# Ethernet.net
KiCad netlist of a schematic drawn in Altium Designer
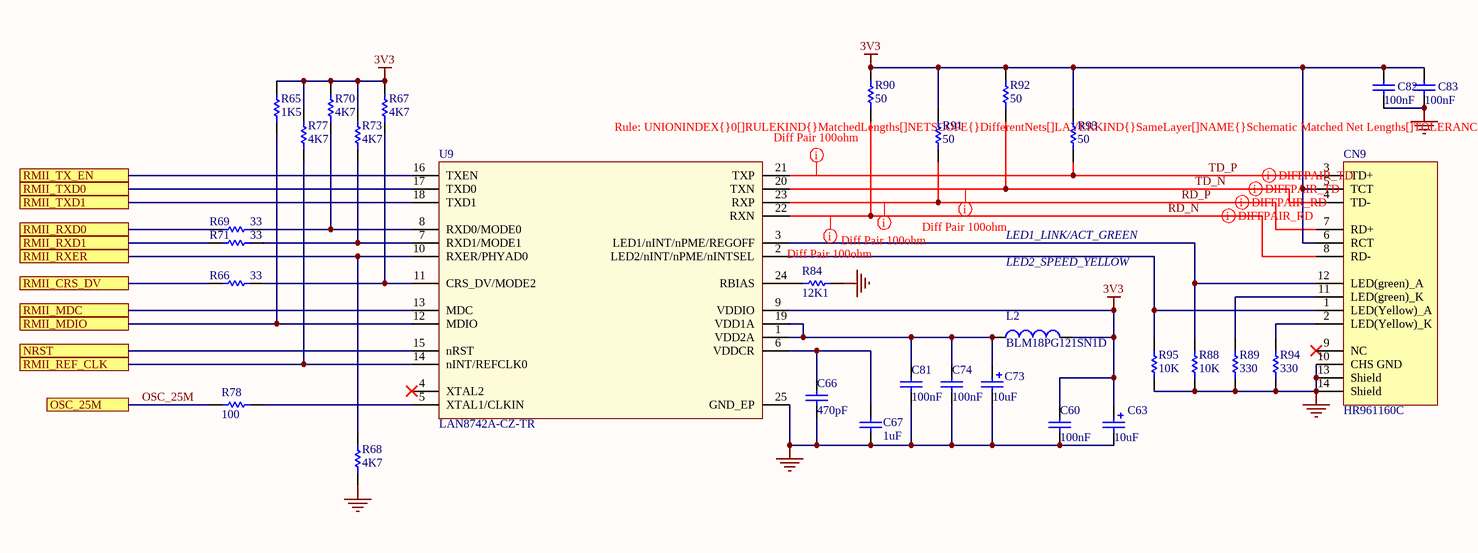
[diagram p0: Ethernet.SchDoc]

(export (version "E")
  (design (tool "Eeschema 10.0.6"))
  (components
    (comp (ref "C60")
      (value "100nF")
      (footprint "0402C")
      (description "Capacitor,100nF,16V,X7R,10%,0402,YAGEO")
      (libsource (lib "MCD_TOOLS") (part "Cap_100nF_X7R_10%_0402"))
    )
    (comp (ref "C63")
      (value "10uF")
      (footprint "TAN-A")
      (description "Polarized Capacitor,10uF,10V,10%,typeA,VISHAY")
      (libsource (lib "MCD_TOOLS") (part "Cap_10uF_POL_10%_TANA"))
    )
    (comp (ref "C66")
      (value "470pF")
      (footprint "0402C")
      (description "Capacitor,470pF,16V,X7R,10%,0402,YAGEO")
      (libsource (lib "MCD_TOOLS") (part "Cap_470pF_X7R_10%_0402"))
    )
    (comp (ref "C67")
      (value "1uF")
      (footprint "0603C")
      (description "Capacitor,1uF,16V,X5R,10%,0603,YAGEO")
      (libsource (lib "MCD_TOOLS") (part "Cap_1uF_X5R_10%_0603"))
    )
    (comp (ref "C73")
      (value "10uF")
      (footprint "TAN-A")
      (description "Polarized Capacitor,10uF,10V,10%,typeA,VISHAY")
      (libsource (lib "MCD_TOOLS") (part "Cap_10uF_POL_10%_TANA"))
    )
    (comp (ref "C74")
      (value "100nF")
      (footprint "0402C")
      (description "Capacitor,100nF,16V,X7R,10%,0402,YAGEO")
      (libsource (lib "MCD_TOOLS") (part "Cap_100nF_X7R_10%_0402"))
    )
    (comp (ref "C81")
      (value "100nF")
      (footprint "0402C")
      (description "Capacitor,100nF,16V,X7R,10%,0402,YAGEO")
      (libsource (lib "MCD_TOOLS") (part "Cap_100nF_X7R_10%_0402"))
    )
    (comp (ref "C82")
      (value "100nF")
      (footprint "0402C")
      (description "Capacitor,100nF,16V,X7R,10%,0402,YAGEO")
      (libsource (lib "MCD_TOOLS") (part "Cap_100nF_X7R_10%_0402"))
    )
    (comp (ref "C83")
      (value "100nF")
      (footprint "0402C")
      (description "Capacitor,100nF,16V,X7R,10%,0402,YAGEO")
      (libsource (lib "MCD_TOOLS") (part "Cap_100nF_X7R_10%_0402"))
    )
    (comp (ref "CN9")
      (value "HR961160C")
      (footprint "RJ45_HR961160C")
      (description "100 Base-TX (Fast Ethernet) SMD RJ45 single port (1x1) with LEDS Integrated Magnetics Connector")
      (libsource (lib "MCD_TOOLS") (part "HR961160C"))
    )
    (comp (ref "L2")
      (value "BLM18PG121SN1D")
      (footprint "0603L")
      (description "Bead,120R,2A,0603,BLM18PG121SN1D,MURATA")
      (libsource (lib "MCD_TOOLS") (part "BEAD_120R_2A_0603"))
    )
    (comp (ref "R65")
      (value "1K5")
      (footprint "0402R")
      (description "Resistor,1K5,0402,1%,YAGEO")
      (libsource (lib "MCD_TOOLS") (part "Res_1K5_1%_0402"))
    )
    (comp (ref "R66")
      (value "33")
      (footprint "0402R")
      (description "Resistor,33,0402,1%,YAGEO")
      (libsource (lib "MCD_TOOLS") (part "Res_33_1%_0402"))
    )
    (comp (ref "R67")
      (value "4K7")
      (footprint "0402R")
      (description "Resistor,4K7,0402,1%,YAGEO")
      (libsource (lib "MCD_TOOLS") (part "Res_4K7_1%_0402"))
    )
    (comp (ref "R68")
      (value "4K7")
      (footprint "0402R")
      (description "Resistor,4K7,0402,1%,YAGEO")
      (libsource (lib "MCD_TOOLS") (part "Res_4K7_1%_0402"))
    )
    (comp (ref "R69")
      (value "33")
      (footprint "0402R")
      (description "Resistor,33,0402,1%,YAGEO")
      (libsource (lib "MCD_TOOLS") (part "Res_33_1%_0402"))
    )
    (comp (ref "R70")
      (value "4K7")
      (footprint "0402R")
      (description "Resistor,4K7,0402,1%,YAGEO")
      (libsource (lib "MCD_TOOLS") (part "Res_4K7_1%_0402"))
    )
    (comp (ref "R71")
      (value "33")
      (footprint "0402R")
      (description "Resistor,33,0402,1%,YAGEO")
      (libsource (lib "MCD_TOOLS") (part "Res_33_1%_0402"))
    )
    (comp (ref "R73")
      (value "4K7")
      (footprint "0402R")
      (description "Resistor,4K7,0402,1%,YAGEO")
      (libsource (lib "MCD_TOOLS") (part "Res_4K7_1%_0402"))
    )
    (comp (ref "R77")
      (value "4K7")
      (footprint "0402R")
      (description "Resistor,4K7,0402,1%,YAGEO")
      (libsource (lib "MCD_TOOLS") (part "Res_4K7_1%_0402"))
    )
    (comp (ref "R78")
      (value "100")
      (footprint "0402R")
      (description "Resistor,100,0402,1%,YAGEO")
      (libsource (lib "MCD_TOOLS") (part "Res_100_1%_0402"))
    )
    (comp (ref "R84")
      (value "12K1")
      (footprint "0603R")
      (description "Resistor,12K1,0603,1%,VISHAY")
      (libsource (lib "MCD_TOOLS") (part "Res_12K1_1%_0603"))
    )
    (comp (ref "R88")
      (value "10K")
      (footprint "0402R")
      (description "Resistor,10K,0402,1%,YAGEO")
      (libsource (lib "MCD_TOOLS") (part "Res_10K_1%_0402"))
    )
    (comp (ref "R89")
      (value "330")
      (footprint "0402R")
      (description "Resistor,330,0402,1%,YAGEO")
      (libsource (lib "MCD_TOOLS") (part "Res_330_1%_0402"))
    )
    (comp (ref "R90")
      (value "50")
      (footprint "0402R")
      (description "Resistor,50,0402,1%,YAGEO")
      (libsource (lib "MCD_TOOLS") (part "Res_50_1%_0402"))
    )
    (comp (ref "R91")
      (value "50")
      (footprint "0402R")
      (description "Resistor,50,0402,1%,YAGEO")
      (libsource (lib "MCD_TOOLS") (part "Res_50_1%_0402"))
    )
    (comp (ref "R92")
      (value "50")
      (footprint "0402R")
      (description "Resistor,50,0402,1%,YAGEO")
      (libsource (lib "MCD_TOOLS") (part "Res_50_1%_0402"))
    )
    (comp (ref "R93")
      (value "50")
      (footprint "0402R")
      (description "Resistor,50,0402,1%,YAGEO")
      (libsource (lib "MCD_TOOLS") (part "Res_50_1%_0402"))
    )
    (comp (ref "R94")
      (value "330")
      (footprint "0402R")
      (description "Resistor,330,0402,1%,YAGEO")
      (libsource (lib "MCD_TOOLS") (part "Res_330_1%_0402"))
    )
    (comp (ref "R95")
      (value "10K")
      (footprint "0402R")
      (description "Resistor,10K,0402,1%,YAGEO")
      (libsource (lib "MCD_TOOLS") (part "Res_10K_1%_0402"))
    )
    (comp (ref "U9")
      (value "LAN8742A-CZ-TR")
      (footprint "QFN24_0R5_4X4")
      (libsource (lib "MCD_TOOLS") (part "LAN8742A-CZ-TR"))
    )
  )
  (nets
    (net (code "1") (name "/NRST") (class "Default")
      (node (ref "U9") (pin "15") (pinfunction "nRST_15") (pintype "passive"))
    )
    (net (code "2") (name "/OSC_25M") (class "Default")
      (node (ref "R78") (pin "1") (pinfunction "1_1") (pintype "passive"))
    )
    (net (code "3") (name "/RD_N") (class "Default")
      (node (ref "CN9") (pin "8") (pinfunction "RD-_8") (pintype "passive"))
      (node (ref "R90") (pin "2") (pinfunction "2_2") (pintype "passive"))
      (node (ref "U9") (pin "22") (pinfunction "RXN_22") (pintype "passive"))
    )
    (net (code "4") (name "/RD_P") (class "Default")
      (node (ref "CN9") (pin "7") (pinfunction "RD+_7") (pintype "passive"))
      (node (ref "R91") (pin "2") (pinfunction "2_2") (pintype "passive"))
      (node (ref "U9") (pin "23") (pinfunction "RXP_23") (pintype "passive"))
    )
    (net (code "5") (name "/RMII_CRS_DV") (class "Default")
      (node (ref "R66") (pin "2") (pinfunction "2_2") (pintype "passive"))
    )
    (net (code "6") (name "/RMII_MDC") (class "Default")
      (node (ref "U9") (pin "13") (pinfunction "MDC_13") (pintype "passive"))
    )
    (net (code "7") (name "/RMII_MDIO") (class "Default")
      (node (ref "R65") (pin "1") (pinfunction "1_1") (pintype "passive"))
      (node (ref "U9") (pin "12") (pinfunction "MDIO_12") (pintype "passive"))
    )
    (net (code "8") (name "/RMII_REF_CLK") (class "Default")
      (node (ref "R77") (pin "1") (pinfunction "1_1") (pintype "passive"))
      (node (ref "U9") (pin "14") (pinfunction "nINT/REFCLK0_14") (pintype "passive"))
    )
    (net (code "9") (name "/RMII_RXD0") (class "Default")
      (node (ref "R69") (pin "2") (pinfunction "2_2") (pintype "passive"))
    )
    (net (code "10") (name "/RMII_RXD1") (class "Default")
      (node (ref "R71") (pin "2") (pinfunction "2_2") (pintype "passive"))
    )
    (net (code "11") (name "/RMII_RXER") (class "Default")
      (node (ref "R68") (pin "2") (pinfunction "2_2") (pintype "passive"))
      (node (ref "U9") (pin "10") (pinfunction "RXER/PHYAD0_10") (pintype "passive"))
    )
    (net (code "12") (name "/RMII_TXD0") (class "Default")
      (node (ref "U9") (pin "17") (pinfunction "TXD0_17") (pintype "passive"))
    )
    (net (code "13") (name "/RMII_TXD1") (class "Default")
      (node (ref "U9") (pin "18") (pinfunction "TXD1_18") (pintype "passive"))
    )
    (net (code "14") (name "/RMII_TX_EN") (class "Default")
      (node (ref "U9") (pin "16") (pinfunction "TXEN_16") (pintype "passive"))
    )
    (net (code "15") (name "/TD_N") (class "Default")
      (node (ref "CN9") (pin "4") (pinfunction "TD-_4") (pintype "passive"))
      (node (ref "R92") (pin "2") (pinfunction "2_2") (pintype "passive"))
      (node (ref "U9") (pin "20") (pinfunction "TXN_20") (pintype "passive"))
    )
    (net (code "16") (name "/TD_P") (class "Default")
      (node (ref "CN9") (pin "3") (pinfunction "TD+_3") (pintype "passive"))
      (node (ref "R93") (pin "2") (pinfunction "2_2") (pintype "passive"))
      (node (ref "U9") (pin "21") (pinfunction "TXP_21") (pintype "passive"))
    )
    (net (code "17") (name "3V3") (class "Default")
      (node (ref "C60") (pin "2") (pinfunction "2_2") (pintype "passive"))
      (node (ref "C63") (pin "1") (pinfunction "1_1") (pintype "passive"))
      (node (ref "C82") (pin "2") (pinfunction "2_2") (pintype "passive"))
      (node (ref "C83") (pin "2") (pinfunction "2_2") (pintype "passive"))
      (node (ref "CN9") (pin "5") (pinfunction "TCT_5") (pintype "passive"))
      (node (ref "CN9") (pin "6") (pinfunction "RCT_6") (pintype "passive"))
      (node (ref "L2") (pin "2") (pinfunction "2_2") (pintype "passive"))
      (node (ref "R65") (pin "2") (pinfunction "2_2") (pintype "passive"))
      (node (ref "R67") (pin "2") (pinfunction "2_2") (pintype "passive"))
      (node (ref "R70") (pin "2") (pinfunction "2_2") (pintype "passive"))
      (node (ref "R73") (pin "2") (pinfunction "2_2") (pintype "passive"))
      (node (ref "R77") (pin "2") (pinfunction "2_2") (pintype "passive"))
      (node (ref "R90") (pin "1") (pinfunction "1_1") (pintype "passive"))
      (node (ref "R91") (pin "1") (pinfunction "1_1") (pintype "passive"))
      (node (ref "R92") (pin "1") (pinfunction "1_1") (pintype "passive"))
      (node (ref "R93") (pin "1") (pinfunction "1_1") (pintype "passive"))
      (node (ref "U9") (pin "9") (pinfunction "VDDIO_9") (pintype "passive"))
    )
    (net (code "18") (name "GND") (class "Default")
      (node (ref "C60") (pin "1") (pinfunction "1_1") (pintype "passive"))
      (node (ref "C63") (pin "2") (pinfunction "2_2") (pintype "passive"))
      (node (ref "C66") (pin "1") (pinfunction "1_1") (pintype "passive"))
      (node (ref "C67") (pin "1") (pinfunction "1_1") (pintype "passive"))
      (node (ref "C73") (pin "2") (pinfunction "2_2") (pintype "passive"))
      (node (ref "C74") (pin "1") (pinfunction "1_1") (pintype "passive"))
      (node (ref "C81") (pin "1") (pinfunction "1_1") (pintype "passive"))
      (node (ref "C82") (pin "1") (pinfunction "1_1") (pintype "passive"))
      (node (ref "C83") (pin "1") (pinfunction "1_1") (pintype "passive"))
      (node (ref "CN9") (pin "10") (pinfunction "CHS_GND_10") (pintype "passive"))
      (node (ref "CN9") (pin "13") (pinfunction "Shield_13") (pintype "passive"))
      (node (ref "CN9") (pin "14") (pinfunction "Shield_14") (pintype "passive"))
      (node (ref "R68") (pin "1") (pinfunction "1_1") (pintype "passive"))
      (node (ref "R84") (pin "2") (pinfunction "2_2") (pintype "passive"))
      (node (ref "R88") (pin "1") (pinfunction "1_1") (pintype "passive"))
      (node (ref "R89") (pin "1") (pinfunction "1_1") (pintype "passive"))
      (node (ref "R94") (pin "1") (pinfunction "1_1") (pintype "passive"))
      (node (ref "R95") (pin "1") (pinfunction "1_1") (pintype "passive"))
      (node (ref "U9") (pin "25") (pinfunction "GND_EP_25") (pintype "passive"))
    )
    (net (code "19") (name "Net-(CN9-LED(Yellow)_A)") (class "Default")
      (node (ref "CN9") (pin "1") (pinfunction "LED(Yellow)_A_1") (pintype "passive"))
      (node (ref "R95") (pin "2") (pinfunction "2_2") (pintype "passive"))
      (node (ref "U9") (pin "2") (pinfunction "LED2/nINT/nPME/nINTSEL_2") (pintype "passive"))
    )
    (net (code "20") (name "Net-(CN9-LED(Yellow)_K)") (class "Default")
      (node (ref "CN9") (pin "2") (pinfunction "LED(Yellow)_K_2") (pintype "passive"))
      (node (ref "R94") (pin "2") (pinfunction "2_2") (pintype "passive"))
    )
    (net (code "21") (name "Net-(CN9-LED(green)_A)") (class "Default")
      (node (ref "CN9") (pin "12") (pinfunction "LED(green)_A_12") (pintype "passive"))
      (node (ref "R88") (pin "2") (pinfunction "2_2") (pintype "passive"))
      (node (ref "U9") (pin "3") (pinfunction "LED1/nINT/nPME/REGOFF_3") (pintype "passive"))
    )
    (net (code "22") (name "Net-(CN9-LED(green)_K)") (class "Default")
      (node (ref "CN9") (pin "11") (pinfunction "LED(green)_K_11") (pintype "passive"))
      (node (ref "R89") (pin "2") (pinfunction "2_2") (pintype "passive"))
    )
    (net (code "23") (name "Net-(U9-CRS_DV{slash}MODE2)") (class "Default")
      (node (ref "R66") (pin "1") (pinfunction "1_1") (pintype "passive"))
      (node (ref "R67") (pin "1") (pinfunction "1_1") (pintype "passive"))
      (node (ref "U9") (pin "11") (pinfunction "CRS_DV/MODE2_11") (pintype "passive"))
    )
    (net (code "24") (name "Net-(U9-RBIAS)") (class "Default")
      (node (ref "R84") (pin "1") (pinfunction "1_1") (pintype "passive"))
      (node (ref "U9") (pin "24") (pinfunction "RBIAS_24") (pintype "passive"))
    )
    (net (code "25") (name "Net-(U9-RXD0{slash}MODE0)") (class "Default")
      (node (ref "R69") (pin "1") (pinfunction "1_1") (pintype "passive"))
      (node (ref "R70") (pin "1") (pinfunction "1_1") (pintype "passive"))
      (node (ref "U9") (pin "8") (pinfunction "RXD0/MODE0_8") (pintype "passive"))
    )
    (net (code "26") (name "Net-(U9-RXD1{slash}MODE1)") (class "Default")
      (node (ref "R71") (pin "1") (pinfunction "1_1") (pintype "passive"))
      (node (ref "R73") (pin "1") (pinfunction "1_1") (pintype "passive"))
      (node (ref "U9") (pin "7") (pinfunction "RXD1/MODE1_7") (pintype "passive"))
    )
    (net (code "27") (name "Net-(U9-VDD1A)") (class "Default")
      (node (ref "C73") (pin "1") (pinfunction "1_1") (pintype "passive"))
      (node (ref "C74") (pin "2") (pinfunction "2_2") (pintype "passive"))
      (node (ref "C81") (pin "2") (pinfunction "2_2") (pintype "passive"))
      (node (ref "L2") (pin "1") (pinfunction "1_1") (pintype "passive"))
      (node (ref "U9") (pin "1") (pinfunction "VDD2A_1") (pintype "passive"))
      (node (ref "U9") (pin "19") (pinfunction "VDD1A_19") (pintype "passive"))
    )
    (net (code "28") (name "Net-(U9-VDDCR)") (class "Default")
      (node (ref "C66") (pin "2") (pinfunction "2_2") (pintype "passive"))
      (node (ref "C67") (pin "2") (pinfunction "2_2") (pintype "passive"))
      (node (ref "U9") (pin "6") (pinfunction "VDDCR_6") (pintype "passive"))
    )
    (net (code "29") (name "Net-(U9-XTAL1{slash}CLKIN)") (class "Default")
      (node (ref "R78") (pin "2") (pinfunction "2_2") (pintype "passive"))
      (node (ref "U9") (pin "5") (pinfunction "XTAL1/CLKIN_5") (pintype "passive"))
    )
    (net (code "30") (name "unconnected-(CN9-NC-Pad9)") (class "Default")
      (node (ref "CN9") (pin "9") (pinfunction "NC_9") (pintype "passive+no_connect"))
    )
    (net (code "31") (name "unconnected-(U9-XTAL2-Pad4)") (class "Default")
      (node (ref "U9") (pin "4") (pinfunction "XTAL2_4") (pintype "passive+no_connect"))
    )
  )
)
